# water_buzzer.net
KiCad netlist of a schematic drawn in EAGLE
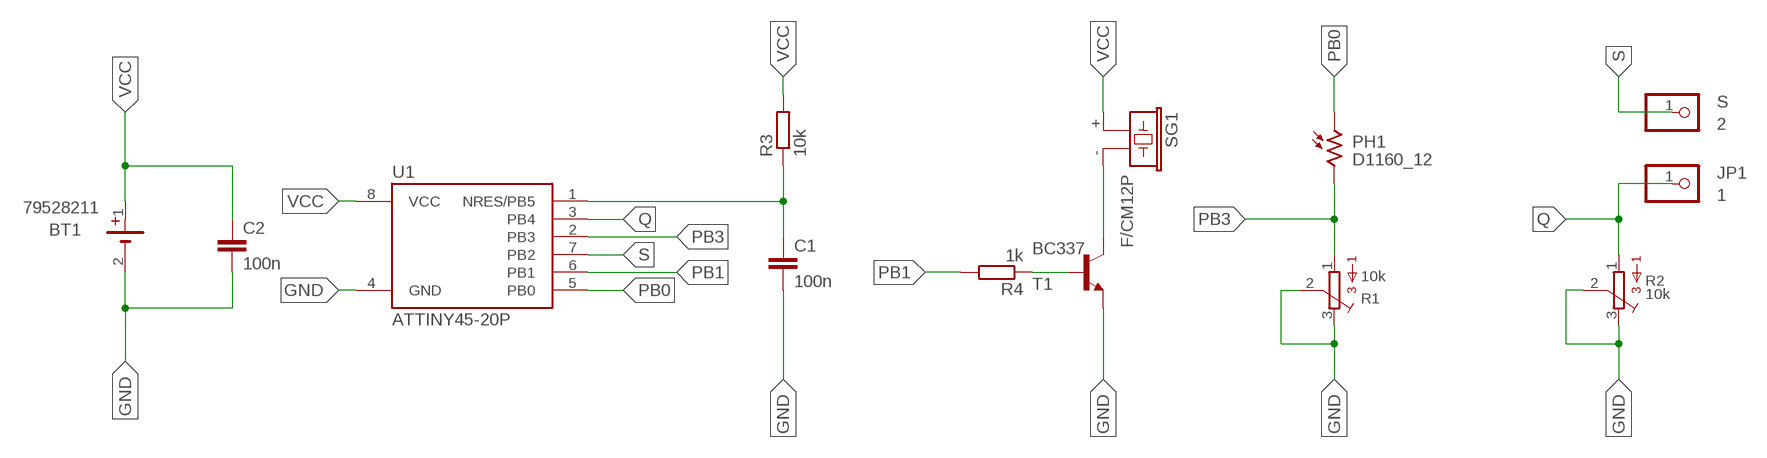
[diagram p0: schematic, sheet 1]

(export (version "E")
  (design (tool "Eeschema 10.0.6"))
  (components
    (comp (ref "BT1")
      (value "79528211")
      (footprint "eagle-import:79528211")
      (fields
        (field (name "DIGIKEY_PART_NO") "732-12326-ND")
        (field (name "MANUFACTURER") "Wurth Electronics Inc.")
        (field (name "CREATED_BY") "PCBLayout.com")
      )
      (libsource (lib "eagle-import") (part "79528211"))
    )
    (comp (ref "C1")
      (value "100n")
      (footprint "eagle-import:C5B2.5")
      (libsource (lib "eagle-import") (part "C5/2.5"))
    )
    (comp (ref "C2")
      (value "100n")
      (footprint "eagle-import:C5B2.5")
      (libsource (lib "eagle-import") (part "C5/2.5"))
    )
    (comp (ref "JP1")
      (value "1")
      (footprint "eagle-import:1X01")
      (libsource (lib "eagle-import") (part "PINHD-1X1"))
    )
    (comp (ref "PH1")
      (value "D1160_12")
      (footprint "eagle-import:D11XX")
      (libsource (lib "eagle-import") (part "D1160_12"))
    )
    (comp (ref "R1")
      (value "10k")
      (footprint "eagle-import:3362H")
      (libsource (lib "eagle-import") (part "3362H"))
    )
    (comp (ref "R2")
      (value "10k")
      (footprint "eagle-import:3362H")
      (libsource (lib "eagle-import") (part "3362H"))
    )
    (comp (ref "R3")
      (value "10k")
      (footprint "eagle-import:0204_7")
      (libsource (lib "eagle-import") (part "R-EU_0204/7"))
    )
    (comp (ref "R4")
      (value "1k")
      (footprint "eagle-import:0204_7")
      (libsource (lib "eagle-import") (part "R-EU_0204/7"))
    )
    (comp (ref "S")
      (value "2")
      (footprint "eagle-import:1X01")
      (libsource (lib "eagle-import") (part "PINHD-1X1"))
    )
    (comp (ref "SG1")
      (value "F/CM12P")
      (footprint "eagle-import:F_CM12P")
      (libsource (lib "eagle-import") (part "F/CM12P"))
    )
    (comp (ref "T1")
      (value "BC337")
      (footprint "eagle-import:TO92")
      (libsource (lib "eagle-import") (part "BC337"))
    )
    (comp (ref "U1")
      (value "ATTINY45-20P")
      (footprint "eagle-import:PDIP08_300MIL")
      (libsource (lib "eagle-import") (part "ATTINY45P-20"))
    )
  )
  (nets
    (net (code "1") (name "GND") (class "Default")
      (node (ref "BT1") (pin "2") (pinfunction "-_2") (pintype "passive"))
      (node (ref "C1") (pin "2") (pinfunction "2_2") (pintype "passive"))
      (node (ref "C2") (pin "2") (pinfunction "2_2") (pintype "passive"))
      (node (ref "R1") (pin "2") (pinfunction "2_2") (pintype "passive"))
      (node (ref "R1") (pin "3") (pinfunction "3_3") (pintype "passive"))
      (node (ref "R2") (pin "2") (pinfunction "2_2") (pintype "passive"))
      (node (ref "R2") (pin "3") (pinfunction "3_3") (pintype "passive"))
      (node (ref "T1") (pin "1") (pinfunction "E_1") (pintype "passive"))
      (node (ref "U1") (pin "4") (pinfunction "GND_4") (pintype "power_in"))
    )
    (net (code "2") (name "Net-(SG1-2)") (class "Default")
      (node (ref "SG1") (pin "-") (pinfunction "2_-") (pintype "passive"))
      (node (ref "T1") (pin "3") (pinfunction "C_3") (pintype "passive"))
    )
    (net (code "3") (name "Net-(T1-B)") (class "Default")
      (node (ref "R4") (pin "1") (pinfunction "1_1") (pintype "passive"))
      (node (ref "T1") (pin "2") (pinfunction "B_2") (pintype "passive"))
    )
    (net (code "4") (name "Net-(U1-NRES{slash}PB5)") (class "Default")
      (node (ref "C1") (pin "1") (pinfunction "1_1") (pintype "passive"))
      (node (ref "R3") (pin "1") (pinfunction "1_1") (pintype "passive"))
      (node (ref "U1") (pin "1") (pinfunction "NRES/PB5_1") (pintype "bidirectional"))
    )
    (net (code "5") (name "PB0") (class "Default")
      (node (ref "PH1") (pin "1") (pinfunction "1_1") (pintype "passive"))
      (node (ref "U1") (pin "5") (pinfunction "PB0_5") (pintype "bidirectional"))
    )
    (net (code "6") (name "PB1") (class "Default")
      (node (ref "R4") (pin "2") (pinfunction "2_2") (pintype "passive"))
      (node (ref "U1") (pin "6") (pinfunction "PB1_6") (pintype "bidirectional"))
    )
    (net (code "7") (name "PB3") (class "Default")
      (node (ref "PH1") (pin "2") (pinfunction "2_2") (pintype "passive"))
      (node (ref "R1") (pin "1") (pinfunction "1_1") (pintype "passive"))
      (node (ref "U1") (pin "2") (pinfunction "PB3_2") (pintype "bidirectional"))
    )
    (net (code "8") (name "Q") (class "Default")
      (node (ref "JP1") (pin "1") (pinfunction "1_1") (pintype "passive"))
      (node (ref "R2") (pin "1") (pinfunction "1_1") (pintype "passive"))
      (node (ref "U1") (pin "3") (pinfunction "PB4_3") (pintype "bidirectional"))
    )
    (net (code "9") (name "S") (class "Default")
      (node (ref "S") (pin "1") (pinfunction "1_1") (pintype "passive"))
      (node (ref "U1") (pin "7") (pinfunction "PB2_7") (pintype "bidirectional"))
    )
    (net (code "10") (name "VCC") (class "Default")
      (node (ref "BT1") (pin "1") (pinfunction "+_1") (pintype "passive"))
      (node (ref "C2") (pin "1") (pinfunction "1_1") (pintype "passive"))
      (node (ref "R3") (pin "2") (pinfunction "2_2") (pintype "passive"))
      (node (ref "SG1") (pin "+") (pinfunction "1_+") (pintype "passive"))
      (node (ref "U1") (pin "8") (pinfunction "VCC_8") (pintype "power_in"))
    )
  )
)
